# Side_2.net
KiCad netlist of a schematic drawn in EAGLE
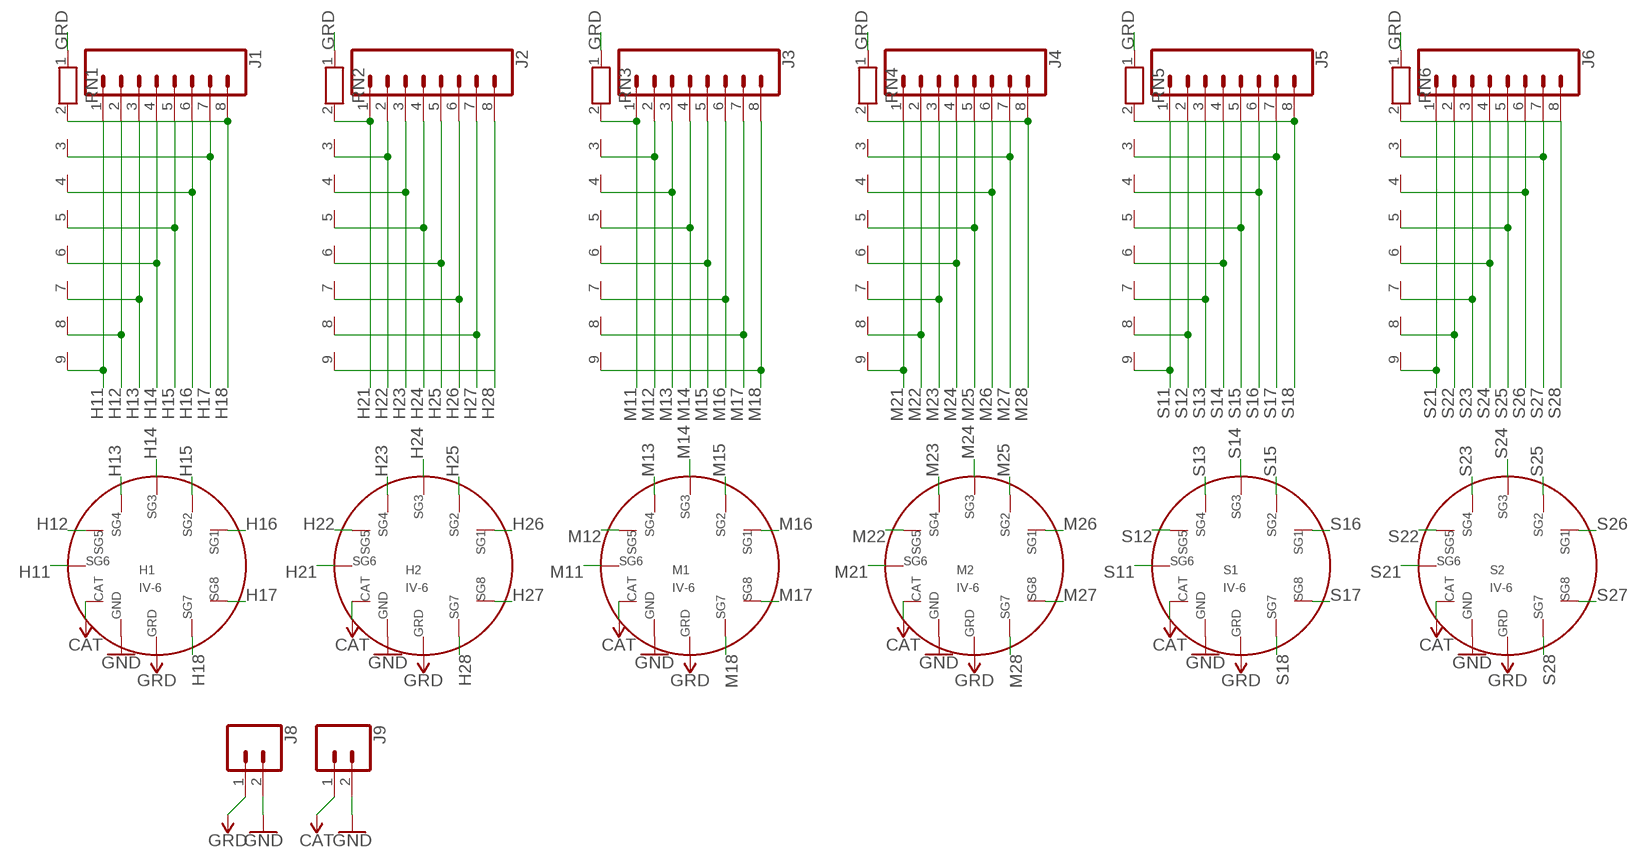
[diagram p0: schematic, sheet 1]

(export (version "E")
  (design (tool "Eeschema 10.0.6"))
  (components
    (comp (ref "H1")
      (value "IV-6")
      (footprint "eagle-import:IV-6")
      (libsource (lib "eagle-import") (part "IV-6"))
    )
    (comp (ref "H2")
      (value "IV-6")
      (footprint "eagle-import:IV-6")
      (libsource (lib "eagle-import") (part "IV-6"))
    )
    (comp (ref "J1")
      (value "CONN_08\"")
      (footprint "eagle-import:1X08")
      (libsource (lib "eagle-import") (part "CONN_08{dblquote}"))
    )
    (comp (ref "J2")
      (value "CONN_08\"")
      (footprint "eagle-import:1X08")
      (libsource (lib "eagle-import") (part "CONN_08{dblquote}"))
    )
    (comp (ref "J3")
      (value "CONN_08\"")
      (footprint "eagle-import:1X08")
      (libsource (lib "eagle-import") (part "CONN_08{dblquote}"))
    )
    (comp (ref "J4")
      (value "CONN_08\"")
      (footprint "eagle-import:1X08")
      (libsource (lib "eagle-import") (part "CONN_08{dblquote}"))
    )
    (comp (ref "J5")
      (value "CONN_08\"")
      (footprint "eagle-import:1X08")
      (libsource (lib "eagle-import") (part "CONN_08{dblquote}"))
    )
    (comp (ref "J6")
      (value "CONN_08\"")
      (footprint "eagle-import:1X08")
      (libsource (lib "eagle-import") (part "CONN_08{dblquote}"))
    )
    (comp (ref "J8")
      (value "CONN_02")
      (footprint "eagle-import:1X02")
      (libsource (lib "eagle-import") (part "CONN_02"))
    )
    (comp (ref "J9")
      (value "CONN_02")
      (footprint "eagle-import:1X02")
      (libsource (lib "eagle-import") (part "CONN_02"))
    )
    (comp (ref "M1")
      (value "IV-6")
      (footprint "eagle-import:IV-6")
      (libsource (lib "eagle-import") (part "IV-6"))
    )
    (comp (ref "M2")
      (value "IV-6")
      (footprint "eagle-import:IV-6")
      (libsource (lib "eagle-import") (part "IV-6"))
    )
    (comp (ref "RN1")
      (value "RN08")
      (footprint "eagle-import:RN-9")
      (libsource (lib "eagle-import") (part "RN08"))
    )
    (comp (ref "RN2")
      (value "RN08")
      (footprint "eagle-import:RN-9")
      (libsource (lib "eagle-import") (part "RN08"))
    )
    (comp (ref "RN3")
      (value "RN08")
      (footprint "eagle-import:RN-9")
      (libsource (lib "eagle-import") (part "RN08"))
    )
    (comp (ref "RN4")
      (value "RN08")
      (footprint "eagle-import:RN-9")
      (libsource (lib "eagle-import") (part "RN08"))
    )
    (comp (ref "RN5")
      (value "RN08")
      (footprint "eagle-import:RN-9")
      (libsource (lib "eagle-import") (part "RN08"))
    )
    (comp (ref "RN6")
      (value "RN08")
      (footprint "eagle-import:RN-9")
      (libsource (lib "eagle-import") (part "RN08"))
    )
    (comp (ref "S1")
      (value "IV-6")
      (footprint "eagle-import:IV-6")
      (libsource (lib "eagle-import") (part "IV-6"))
    )
    (comp (ref "S2")
      (value "IV-6")
      (footprint "eagle-import:IV-6")
      (libsource (lib "eagle-import") (part "IV-6"))
    )
  )
  (nets
    (net (code "1") (name "/H11") (class "Default")
      (node (ref "H1") (pin "SG6") (pinfunction "SG6_SG6") (pintype "bidirectional"))
      (node (ref "J1") (pin "1") (pinfunction "1_1") (pintype "passive"))
      (node (ref "RN1") (pin "9") (pinfunction "9_9") (pintype "passive"))
    )
    (net (code "2") (name "/H12") (class "Default")
      (node (ref "H1") (pin "SG5") (pinfunction "SG5_SG5") (pintype "bidirectional"))
      (node (ref "J1") (pin "2") (pinfunction "2_2") (pintype "passive"))
      (node (ref "RN1") (pin "8") (pinfunction "8_8") (pintype "passive"))
    )
    (net (code "3") (name "/H13") (class "Default")
      (node (ref "H1") (pin "SG4") (pinfunction "SG4_SG4") (pintype "bidirectional"))
      (node (ref "J1") (pin "3") (pinfunction "3_3") (pintype "passive"))
      (node (ref "RN1") (pin "7") (pinfunction "7_7") (pintype "passive"))
    )
    (net (code "4") (name "/H14") (class "Default")
      (node (ref "H1") (pin "SG3") (pinfunction "SG3_SG3") (pintype "bidirectional"))
      (node (ref "J1") (pin "4") (pinfunction "4_4") (pintype "passive"))
      (node (ref "RN1") (pin "6") (pinfunction "6_6") (pintype "passive"))
    )
    (net (code "5") (name "/H15") (class "Default")
      (node (ref "H1") (pin "SG2") (pinfunction "SG2_SG2") (pintype "bidirectional"))
      (node (ref "J1") (pin "5") (pinfunction "5_5") (pintype "passive"))
      (node (ref "RN1") (pin "5") (pinfunction "5_5") (pintype "passive"))
    )
    (net (code "6") (name "/H16") (class "Default")
      (node (ref "H1") (pin "SG1") (pinfunction "SG1_SG1") (pintype "bidirectional"))
      (node (ref "J1") (pin "6") (pinfunction "6_6") (pintype "passive"))
      (node (ref "RN1") (pin "4") (pinfunction "4_4") (pintype "passive"))
    )
    (net (code "7") (name "/H17") (class "Default")
      (node (ref "H1") (pin "SG8") (pinfunction "SG8_SG8") (pintype "bidirectional"))
      (node (ref "J1") (pin "7") (pinfunction "7_7") (pintype "passive"))
      (node (ref "RN1") (pin "3") (pinfunction "3_3") (pintype "passive"))
    )
    (net (code "8") (name "/H18") (class "Default")
      (node (ref "H1") (pin "SG7") (pinfunction "SG7_SG7") (pintype "bidirectional"))
      (node (ref "J1") (pin "8") (pinfunction "8_8") (pintype "passive"))
      (node (ref "RN1") (pin "2") (pinfunction "2_2") (pintype "passive"))
    )
    (net (code "9") (name "/H21") (class "Default")
      (node (ref "H2") (pin "SG6") (pinfunction "SG6_SG6") (pintype "bidirectional"))
      (node (ref "J2") (pin "1") (pinfunction "1_1") (pintype "passive"))
      (node (ref "RN2") (pin "2") (pinfunction "2_2") (pintype "passive"))
    )
    (net (code "10") (name "/H22") (class "Default")
      (node (ref "H2") (pin "SG5") (pinfunction "SG5_SG5") (pintype "bidirectional"))
      (node (ref "J2") (pin "2") (pinfunction "2_2") (pintype "passive"))
      (node (ref "RN2") (pin "3") (pinfunction "3_3") (pintype "passive"))
    )
    (net (code "11") (name "/H23") (class "Default")
      (node (ref "H2") (pin "SG4") (pinfunction "SG4_SG4") (pintype "bidirectional"))
      (node (ref "J2") (pin "3") (pinfunction "3_3") (pintype "passive"))
      (node (ref "RN2") (pin "4") (pinfunction "4_4") (pintype "passive"))
    )
    (net (code "12") (name "/H24") (class "Default")
      (node (ref "H2") (pin "SG3") (pinfunction "SG3_SG3") (pintype "bidirectional"))
      (node (ref "J2") (pin "4") (pinfunction "4_4") (pintype "passive"))
      (node (ref "RN2") (pin "5") (pinfunction "5_5") (pintype "passive"))
    )
    (net (code "13") (name "/H25") (class "Default")
      (node (ref "H2") (pin "SG2") (pinfunction "SG2_SG2") (pintype "bidirectional"))
      (node (ref "J2") (pin "5") (pinfunction "5_5") (pintype "passive"))
      (node (ref "RN2") (pin "6") (pinfunction "6_6") (pintype "passive"))
    )
    (net (code "14") (name "/H26") (class "Default")
      (node (ref "H2") (pin "SG1") (pinfunction "SG1_SG1") (pintype "bidirectional"))
      (node (ref "J2") (pin "6") (pinfunction "6_6") (pintype "passive"))
      (node (ref "RN2") (pin "7") (pinfunction "7_7") (pintype "passive"))
    )
    (net (code "15") (name "/H27") (class "Default")
      (node (ref "H2") (pin "SG8") (pinfunction "SG8_SG8") (pintype "bidirectional"))
      (node (ref "J2") (pin "7") (pinfunction "7_7") (pintype "passive"))
      (node (ref "RN2") (pin "8") (pinfunction "8_8") (pintype "passive"))
    )
    (net (code "16") (name "/H28") (class "Default")
      (node (ref "H2") (pin "SG7") (pinfunction "SG7_SG7") (pintype "bidirectional"))
      (node (ref "J2") (pin "8") (pinfunction "8_8") (pintype "passive"))
      (node (ref "RN2") (pin "9") (pinfunction "9_9") (pintype "passive"))
    )
    (net (code "17") (name "/M11") (class "Default")
      (node (ref "J3") (pin "1") (pinfunction "1_1") (pintype "passive"))
      (node (ref "M1") (pin "SG6") (pinfunction "SG6_SG6") (pintype "bidirectional"))
      (node (ref "RN3") (pin "2") (pinfunction "2_2") (pintype "passive"))
    )
    (net (code "18") (name "/M12") (class "Default")
      (node (ref "J3") (pin "2") (pinfunction "2_2") (pintype "passive"))
      (node (ref "M1") (pin "SG5") (pinfunction "SG5_SG5") (pintype "bidirectional"))
      (node (ref "RN3") (pin "3") (pinfunction "3_3") (pintype "passive"))
    )
    (net (code "19") (name "/M13") (class "Default")
      (node (ref "J3") (pin "3") (pinfunction "3_3") (pintype "passive"))
      (node (ref "M1") (pin "SG4") (pinfunction "SG4_SG4") (pintype "bidirectional"))
      (node (ref "RN3") (pin "4") (pinfunction "4_4") (pintype "passive"))
    )
    (net (code "20") (name "/M14") (class "Default")
      (node (ref "J3") (pin "4") (pinfunction "4_4") (pintype "passive"))
      (node (ref "M1") (pin "SG3") (pinfunction "SG3_SG3") (pintype "bidirectional"))
      (node (ref "RN3") (pin "5") (pinfunction "5_5") (pintype "passive"))
    )
    (net (code "21") (name "/M15") (class "Default")
      (node (ref "J3") (pin "5") (pinfunction "5_5") (pintype "passive"))
      (node (ref "M1") (pin "SG2") (pinfunction "SG2_SG2") (pintype "bidirectional"))
      (node (ref "RN3") (pin "6") (pinfunction "6_6") (pintype "passive"))
    )
    (net (code "22") (name "/M16") (class "Default")
      (node (ref "J3") (pin "6") (pinfunction "6_6") (pintype "passive"))
      (node (ref "M1") (pin "SG1") (pinfunction "SG1_SG1") (pintype "bidirectional"))
      (node (ref "RN3") (pin "7") (pinfunction "7_7") (pintype "passive"))
    )
    (net (code "23") (name "/M17") (class "Default")
      (node (ref "J3") (pin "7") (pinfunction "7_7") (pintype "passive"))
      (node (ref "M1") (pin "SG8") (pinfunction "SG8_SG8") (pintype "bidirectional"))
      (node (ref "RN3") (pin "8") (pinfunction "8_8") (pintype "passive"))
    )
    (net (code "24") (name "/M18") (class "Default")
      (node (ref "J3") (pin "8") (pinfunction "8_8") (pintype "passive"))
      (node (ref "M1") (pin "SG7") (pinfunction "SG7_SG7") (pintype "bidirectional"))
      (node (ref "RN3") (pin "9") (pinfunction "9_9") (pintype "passive"))
    )
    (net (code "25") (name "/M21") (class "Default")
      (node (ref "J4") (pin "1") (pinfunction "1_1") (pintype "passive"))
      (node (ref "M2") (pin "SG6") (pinfunction "SG6_SG6") (pintype "bidirectional"))
      (node (ref "RN4") (pin "9") (pinfunction "9_9") (pintype "passive"))
    )
    (net (code "26") (name "/M22") (class "Default")
      (node (ref "J4") (pin "2") (pinfunction "2_2") (pintype "passive"))
      (node (ref "M2") (pin "SG5") (pinfunction "SG5_SG5") (pintype "bidirectional"))
      (node (ref "RN4") (pin "8") (pinfunction "8_8") (pintype "passive"))
    )
    (net (code "27") (name "/M23") (class "Default")
      (node (ref "J4") (pin "3") (pinfunction "3_3") (pintype "passive"))
      (node (ref "M2") (pin "SG4") (pinfunction "SG4_SG4") (pintype "bidirectional"))
      (node (ref "RN4") (pin "7") (pinfunction "7_7") (pintype "passive"))
    )
    (net (code "28") (name "/M24") (class "Default")
      (node (ref "J4") (pin "4") (pinfunction "4_4") (pintype "passive"))
      (node (ref "M2") (pin "SG3") (pinfunction "SG3_SG3") (pintype "bidirectional"))
      (node (ref "RN4") (pin "6") (pinfunction "6_6") (pintype "passive"))
    )
    (net (code "29") (name "/M25") (class "Default")
      (node (ref "J4") (pin "5") (pinfunction "5_5") (pintype "passive"))
      (node (ref "M2") (pin "SG2") (pinfunction "SG2_SG2") (pintype "bidirectional"))
      (node (ref "RN4") (pin "5") (pinfunction "5_5") (pintype "passive"))
    )
    (net (code "30") (name "/M26") (class "Default")
      (node (ref "J4") (pin "6") (pinfunction "6_6") (pintype "passive"))
      (node (ref "M2") (pin "SG1") (pinfunction "SG1_SG1") (pintype "bidirectional"))
      (node (ref "RN4") (pin "4") (pinfunction "4_4") (pintype "passive"))
    )
    (net (code "31") (name "/M27") (class "Default")
      (node (ref "J4") (pin "7") (pinfunction "7_7") (pintype "passive"))
      (node (ref "M2") (pin "SG8") (pinfunction "SG8_SG8") (pintype "bidirectional"))
      (node (ref "RN4") (pin "3") (pinfunction "3_3") (pintype "passive"))
    )
    (net (code "32") (name "/M28") (class "Default")
      (node (ref "J4") (pin "8") (pinfunction "8_8") (pintype "passive"))
      (node (ref "M2") (pin "SG7") (pinfunction "SG7_SG7") (pintype "bidirectional"))
      (node (ref "RN4") (pin "2") (pinfunction "2_2") (pintype "passive"))
    )
    (net (code "33") (name "/S11") (class "Default")
      (node (ref "J5") (pin "1") (pinfunction "1_1") (pintype "passive"))
      (node (ref "RN5") (pin "9") (pinfunction "9_9") (pintype "passive"))
      (node (ref "S1") (pin "SG6") (pinfunction "SG6_SG6") (pintype "bidirectional"))
    )
    (net (code "34") (name "/S12") (class "Default")
      (node (ref "J5") (pin "2") (pinfunction "2_2") (pintype "passive"))
      (node (ref "RN5") (pin "8") (pinfunction "8_8") (pintype "passive"))
      (node (ref "S1") (pin "SG5") (pinfunction "SG5_SG5") (pintype "bidirectional"))
    )
    (net (code "35") (name "/S13") (class "Default")
      (node (ref "J5") (pin "3") (pinfunction "3_3") (pintype "passive"))
      (node (ref "RN5") (pin "7") (pinfunction "7_7") (pintype "passive"))
      (node (ref "S1") (pin "SG4") (pinfunction "SG4_SG4") (pintype "bidirectional"))
    )
    (net (code "36") (name "/S14") (class "Default")
      (node (ref "J5") (pin "4") (pinfunction "4_4") (pintype "passive"))
      (node (ref "RN5") (pin "6") (pinfunction "6_6") (pintype "passive"))
      (node (ref "S1") (pin "SG3") (pinfunction "SG3_SG3") (pintype "bidirectional"))
    )
    (net (code "37") (name "/S15") (class "Default")
      (node (ref "J5") (pin "5") (pinfunction "5_5") (pintype "passive"))
      (node (ref "RN5") (pin "5") (pinfunction "5_5") (pintype "passive"))
      (node (ref "S1") (pin "SG2") (pinfunction "SG2_SG2") (pintype "bidirectional"))
    )
    (net (code "38") (name "/S16") (class "Default")
      (node (ref "J5") (pin "6") (pinfunction "6_6") (pintype "passive"))
      (node (ref "RN5") (pin "4") (pinfunction "4_4") (pintype "passive"))
      (node (ref "S1") (pin "SG1") (pinfunction "SG1_SG1") (pintype "bidirectional"))
    )
    (net (code "39") (name "/S17") (class "Default")
      (node (ref "J5") (pin "7") (pinfunction "7_7") (pintype "passive"))
      (node (ref "RN5") (pin "3") (pinfunction "3_3") (pintype "passive"))
      (node (ref "S1") (pin "SG8") (pinfunction "SG8_SG8") (pintype "bidirectional"))
    )
    (net (code "40") (name "/S18") (class "Default")
      (node (ref "J5") (pin "8") (pinfunction "8_8") (pintype "passive"))
      (node (ref "RN5") (pin "2") (pinfunction "2_2") (pintype "passive"))
      (node (ref "S1") (pin "SG7") (pinfunction "SG7_SG7") (pintype "bidirectional"))
    )
    (net (code "41") (name "/S21") (class "Default")
      (node (ref "J6") (pin "1") (pinfunction "1_1") (pintype "passive"))
      (node (ref "RN6") (pin "9") (pinfunction "9_9") (pintype "passive"))
      (node (ref "S2") (pin "SG6") (pinfunction "SG6_SG6") (pintype "bidirectional"))
    )
    (net (code "42") (name "/S22") (class "Default")
      (node (ref "J6") (pin "2") (pinfunction "2_2") (pintype "passive"))
      (node (ref "RN6") (pin "8") (pinfunction "8_8") (pintype "passive"))
      (node (ref "S2") (pin "SG5") (pinfunction "SG5_SG5") (pintype "bidirectional"))
    )
    (net (code "43") (name "/S23") (class "Default")
      (node (ref "J6") (pin "3") (pinfunction "3_3") (pintype "passive"))
      (node (ref "RN6") (pin "7") (pinfunction "7_7") (pintype "passive"))
      (node (ref "S2") (pin "SG4") (pinfunction "SG4_SG4") (pintype "bidirectional"))
    )
    (net (code "44") (name "/S24") (class "Default")
      (node (ref "J6") (pin "4") (pinfunction "4_4") (pintype "passive"))
      (node (ref "RN6") (pin "6") (pinfunction "6_6") (pintype "passive"))
      (node (ref "S2") (pin "SG3") (pinfunction "SG3_SG3") (pintype "bidirectional"))
    )
    (net (code "45") (name "/S25") (class "Default")
      (node (ref "J6") (pin "5") (pinfunction "5_5") (pintype "passive"))
      (node (ref "RN6") (pin "5") (pinfunction "5_5") (pintype "passive"))
      (node (ref "S2") (pin "SG2") (pinfunction "SG2_SG2") (pintype "bidirectional"))
    )
    (net (code "46") (name "/S26") (class "Default")
      (node (ref "J6") (pin "6") (pinfunction "6_6") (pintype "passive"))
      (node (ref "RN6") (pin "4") (pinfunction "4_4") (pintype "passive"))
      (node (ref "S2") (pin "SG1") (pinfunction "SG1_SG1") (pintype "bidirectional"))
    )
    (net (code "47") (name "/S27") (class "Default")
      (node (ref "J6") (pin "7") (pinfunction "7_7") (pintype "passive"))
      (node (ref "RN6") (pin "3") (pinfunction "3_3") (pintype "passive"))
      (node (ref "S2") (pin "SG8") (pinfunction "SG8_SG8") (pintype "bidirectional"))
    )
    (net (code "48") (name "/S28") (class "Default")
      (node (ref "J6") (pin "8") (pinfunction "8_8") (pintype "passive"))
      (node (ref "RN6") (pin "2") (pinfunction "2_2") (pintype "passive"))
      (node (ref "S2") (pin "SG7") (pinfunction "SG7_SG7") (pintype "bidirectional"))
    )
    (net (code "49") (name "CAT") (class "Default")
      (node (ref "H1") (pin "CAT") (pinfunction "CAT_CAT") (pintype "bidirectional"))
      (node (ref "H2") (pin "CAT") (pinfunction "CAT_CAT") (pintype "bidirectional"))
      (node (ref "J9") (pin "1") (pinfunction "1_1") (pintype "passive"))
      (node (ref "M1") (pin "CAT") (pinfunction "CAT_CAT") (pintype "bidirectional"))
      (node (ref "M2") (pin "CAT") (pinfunction "CAT_CAT") (pintype "bidirectional"))
      (node (ref "S1") (pin "CAT") (pinfunction "CAT_CAT") (pintype "bidirectional"))
      (node (ref "S2") (pin "CAT") (pinfunction "CAT_CAT") (pintype "bidirectional"))
    )
    (net (code "50") (name "GND") (class "Default")
      (node (ref "H1") (pin "GND") (pinfunction "GND_GND") (pintype "bidirectional"))
      (node (ref "H2") (pin "GND") (pinfunction "GND_GND") (pintype "bidirectional"))
      (node (ref "J8") (pin "2") (pinfunction "2_2") (pintype "passive"))
      (node (ref "J9") (pin "2") (pinfunction "2_2") (pintype "passive"))
      (node (ref "M1") (pin "GND") (pinfunction "GND_GND") (pintype "bidirectional"))
      (node (ref "M2") (pin "GND") (pinfunction "GND_GND") (pintype "bidirectional"))
      (node (ref "S1") (pin "GND") (pinfunction "GND_GND") (pintype "bidirectional"))
      (node (ref "S2") (pin "GND") (pinfunction "GND_GND") (pintype "bidirectional"))
    )
    (net (code "51") (name "GRD") (class "Default")
      (node (ref "H1") (pin "GRD") (pinfunction "GRD_GRD") (pintype "bidirectional"))
      (node (ref "H2") (pin "GRD") (pinfunction "GRD_GRD") (pintype "bidirectional"))
      (node (ref "J8") (pin "1") (pinfunction "1_1") (pintype "passive"))
      (node (ref "M1") (pin "GRD") (pinfunction "GRD_GRD") (pintype "bidirectional"))
      (node (ref "M2") (pin "GRD") (pinfunction "GRD_GRD") (pintype "bidirectional"))
      (node (ref "RN1") (pin "1") (pinfunction "1_1") (pintype "passive"))
      (node (ref "RN2") (pin "1") (pinfunction "1_1") (pintype "passive"))
      (node (ref "RN3") (pin "1") (pinfunction "1_1") (pintype "passive"))
      (node (ref "RN4") (pin "1") (pinfunction "1_1") (pintype "passive"))
      (node (ref "RN5") (pin "1") (pinfunction "1_1") (pintype "passive"))
      (node (ref "RN6") (pin "1") (pinfunction "1_1") (pintype "passive"))
      (node (ref "S1") (pin "GRD") (pinfunction "GRD_GRD") (pintype "bidirectional"))
      (node (ref "S2") (pin "GRD") (pinfunction "GRD_GRD") (pintype "bidirectional"))
    )
  )
)
